# 17_PM8916_LDO.net
KiCad netlist of a schematic drawn in Altium Designer
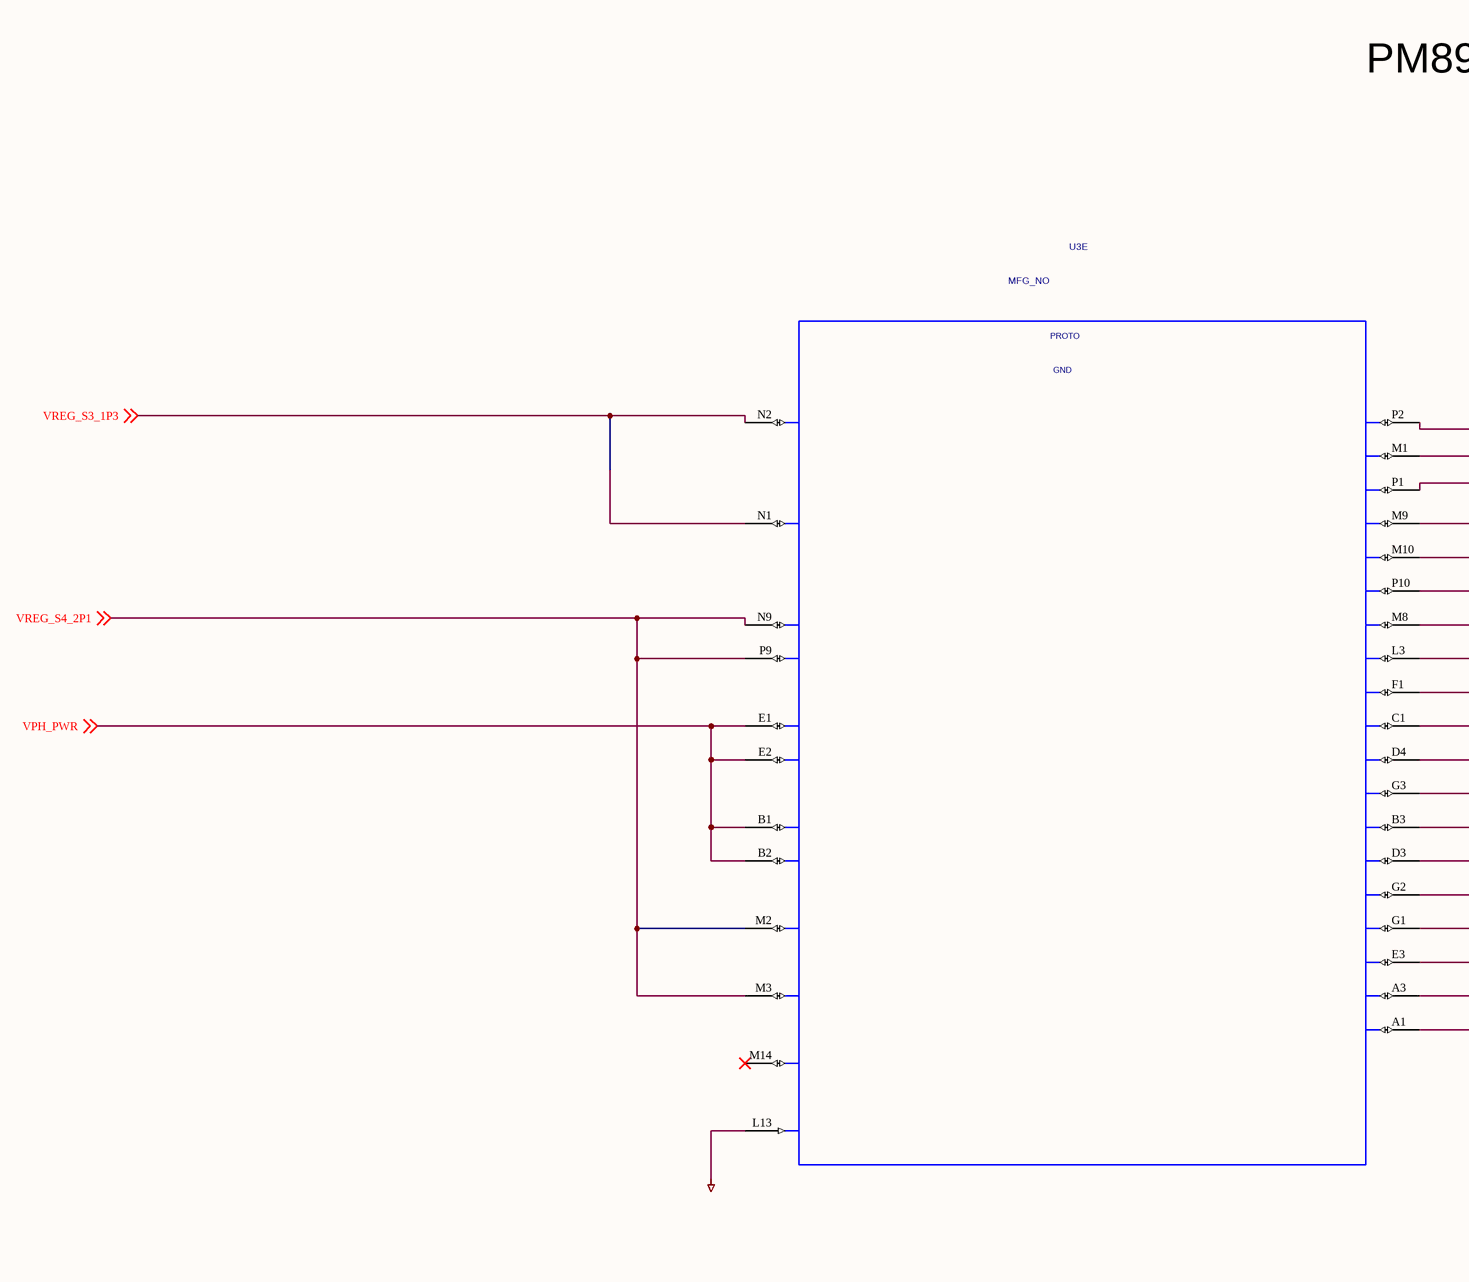
[diagram p0: 17 PM8916_LDO.SchDoc, top left]
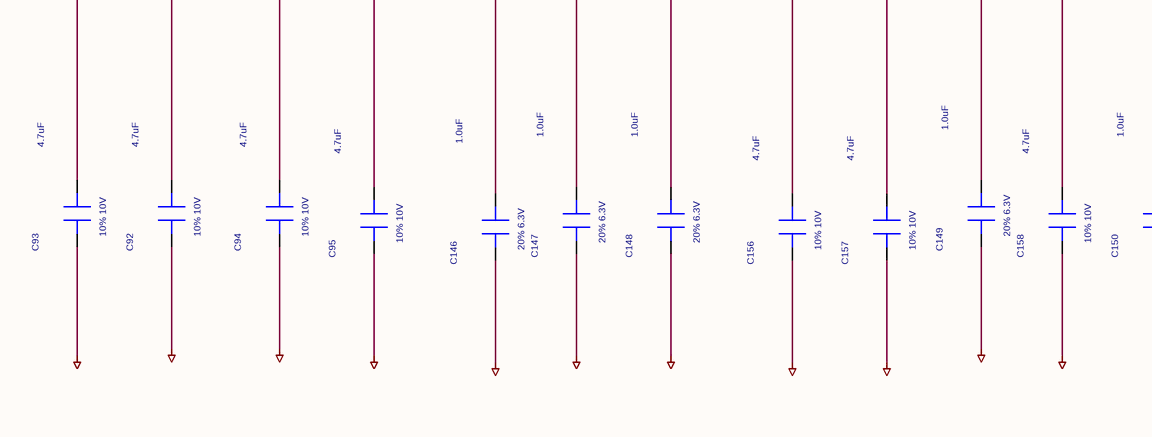
[diagram p1: 17 PM8916_LDO.SchDoc, top middle]
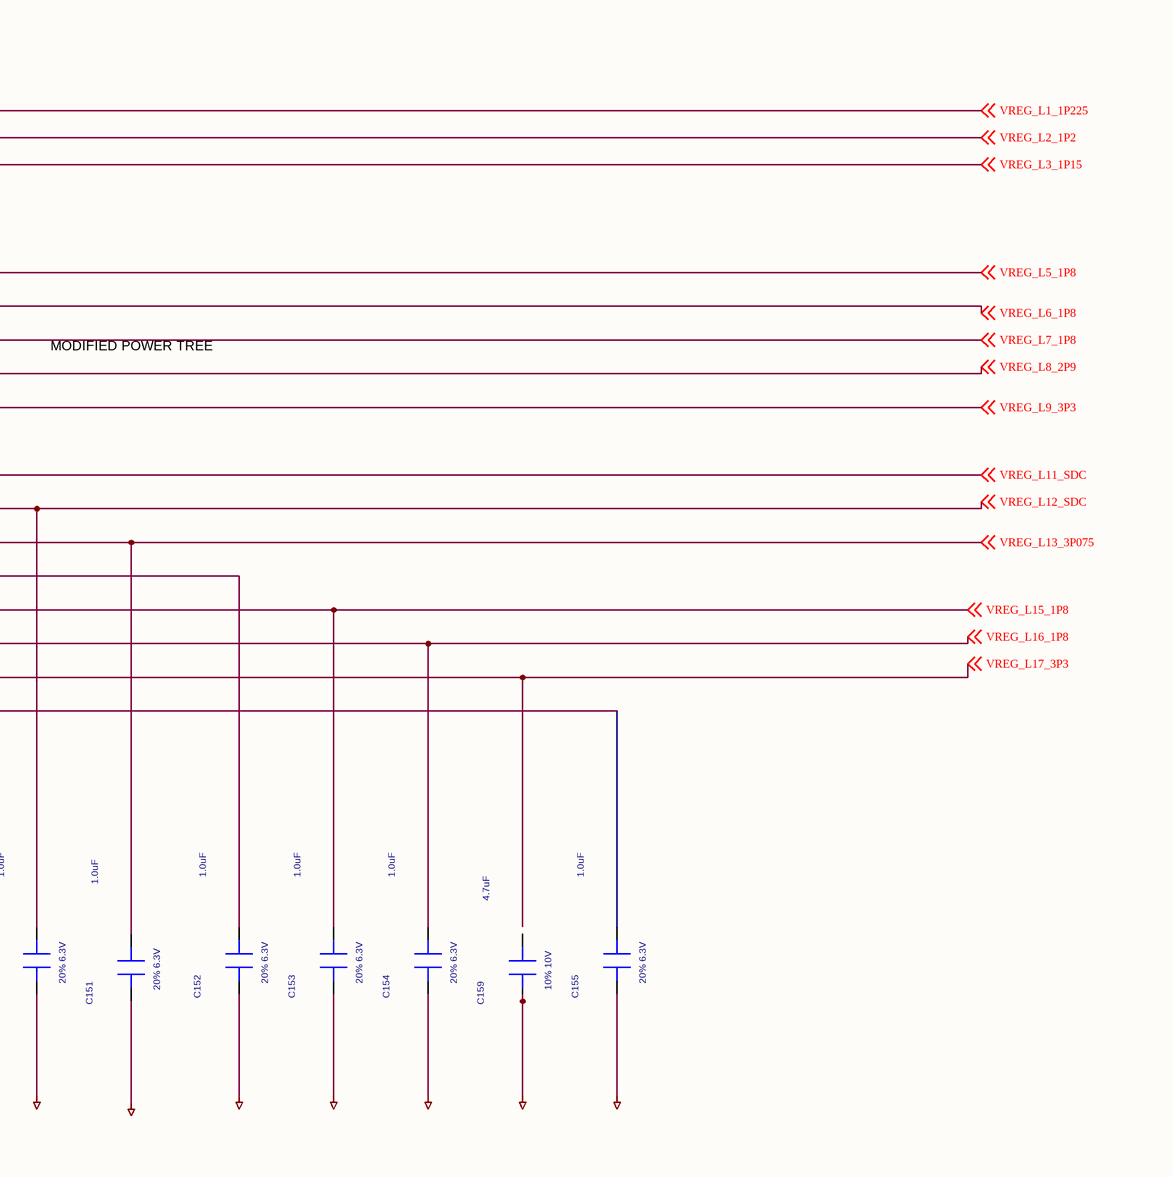
[diagram p2: 17 PM8916_LDO.SchDoc, top right]
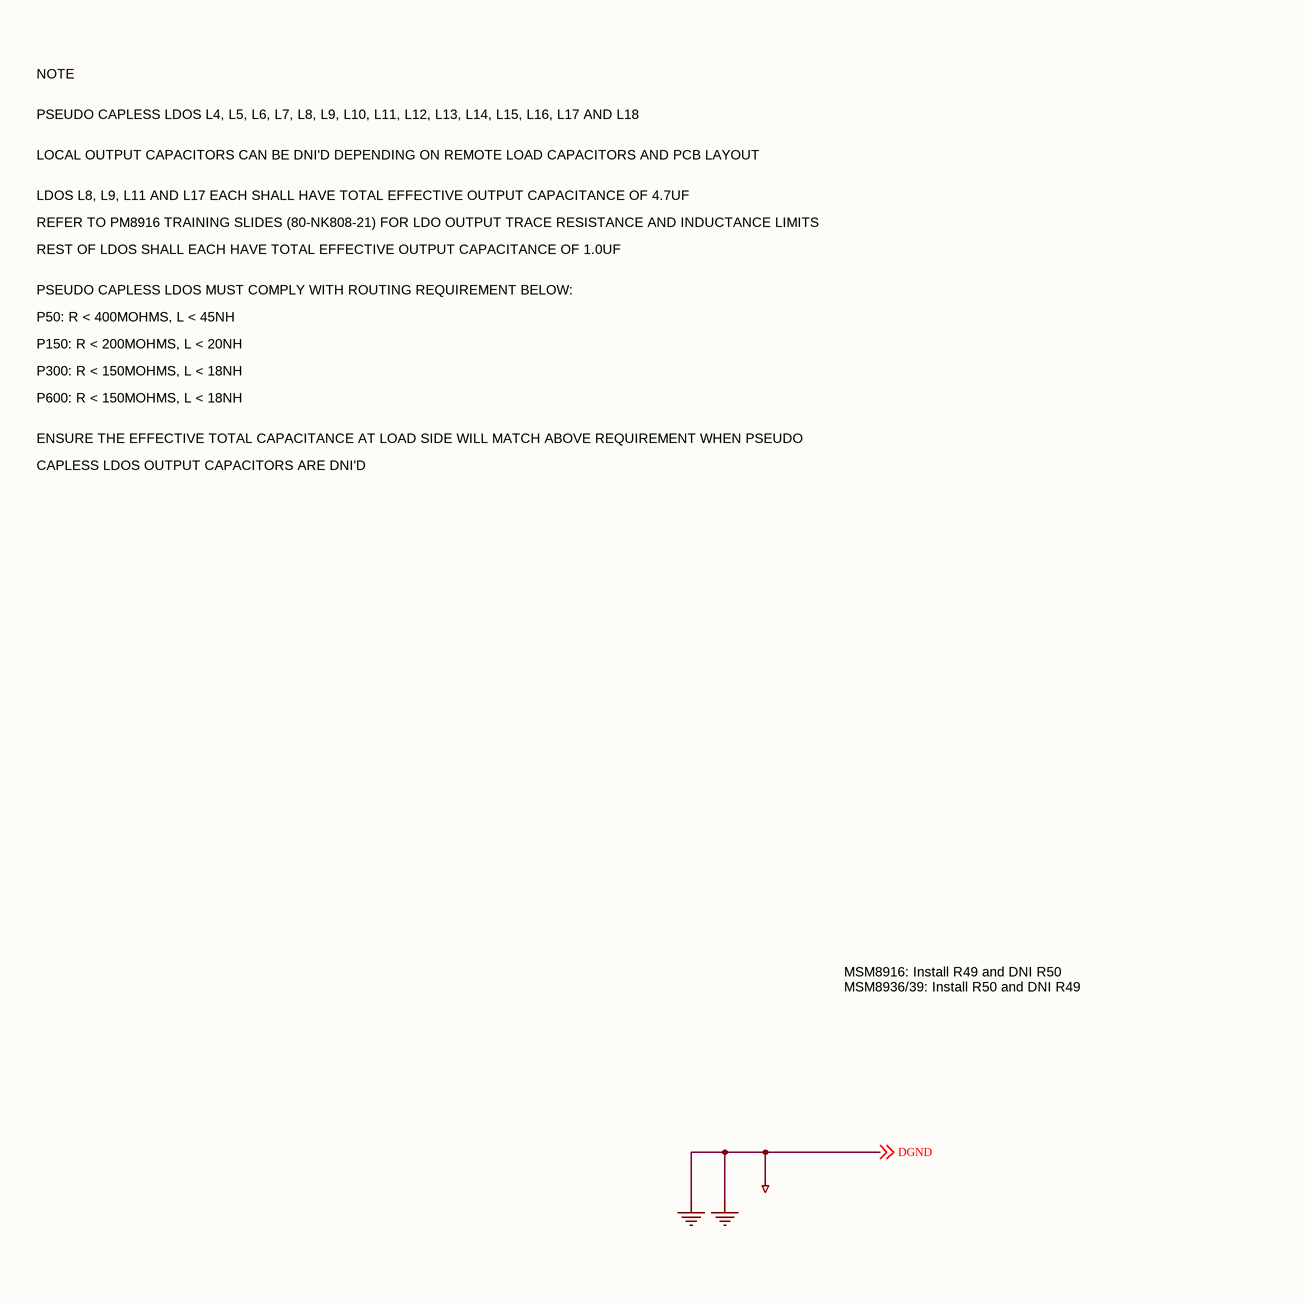
[diagram p3: 17 PM8916_LDO.SchDoc, bottom left]
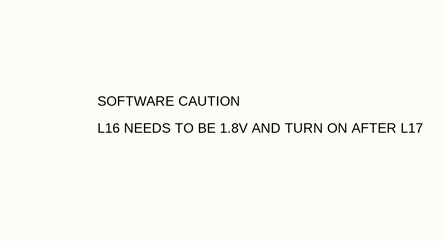
[diagram p4: 17 PM8916_LDO.SchDoc, bottom middle]
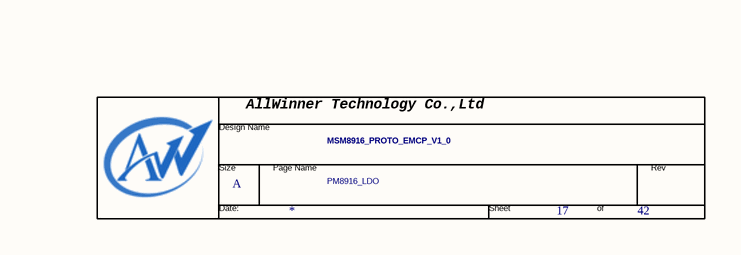
[diagram p5: 17 PM8916_LDO.SchDoc, bottom right]

(export (version "E")
  (design (tool "Eeschema 10.0.6"))
  (components
    (comp (ref "*")
      (value "TitleBlock0-AW")
      (fields
        (field (name "PAGE COUNT") "42")
        (field (name "PAGE NUMBER") "17")
        (field (name "PAGE SIZE") "A")
        (field (name "TITLE") "MSM8916_PROTO_EMCP_V1_0")
        (field (name "DOC") "PM8916_LDO")
      )
      (libsource (lib "*") (part "TitleBlock0-AW"))
    )
    (comp (ref "C92")
      (value "4.7uF")
      (fields (field (name "TOLERANCE") "10% 10V") (field (name "PART_NUMBER") "MCN_NO"))
      (libsource (lib "MSM8916_DRAM_PMIC_REF_Library") (part "CAP#1"))
    )
    (comp (ref "C93")
      (value "4.7uF")
      (fields (field (name "TOLERANCE") "10% 10V") (field (name "PART_NUMBER") "MCN_NO"))
      (libsource (lib "MSM8916_DRAM_PMIC_REF_Library") (part "CAP#1"))
    )
    (comp (ref "C94")
      (value "4.7uF")
      (fields (field (name "TOLERANCE") "10% 10V") (field (name "PART_NUMBER") "MCN_NO"))
      (libsource (lib "MSM8916_DRAM_PMIC_REF_Library") (part "CAP#1"))
    )
    (comp (ref "C95")
      (value "4.7uF")
      (fields (field (name "TOLERANCE") "10% 10V") (field (name "PART_NUMBER") "MCN_NO"))
      (libsource (lib "MSM8916_DRAM_PMIC_REF_Library") (part "CAP#1"))
    )
    (comp (ref "C146")
      (value "1.0uF")
      (fields (field (name "TOLERANCE") "20% 6.3V") (field (name "PART_NUMBER") "MCN_NO"))
      (libsource (lib "MSM8916_DRAM_PMIC_REF_Library") (part "CAP#1"))
    )
    (comp (ref "C147")
      (value "1.0uF")
      (fields (field (name "TOLERANCE") "20% 6.3V") (field (name "PART_NUMBER") "MCN_NO"))
      (libsource (lib "MSM8916_DRAM_PMIC_REF_Library") (part "CAP#1"))
    )
    (comp (ref "C148")
      (value "1.0uF")
      (fields (field (name "TOLERANCE") "20% 6.3V") (field (name "PART_NUMBER") "MCN_NO"))
      (libsource (lib "MSM8916_DRAM_PMIC_REF_Library") (part "CAP#1"))
    )
    (comp (ref "C149")
      (value "1.0uF")
      (fields (field (name "TOLERANCE") "20% 6.3V") (field (name "PART_NUMBER") "MCN_NO"))
      (libsource (lib "MSM8916_DRAM_PMIC_REF_Library") (part "CAP#1"))
    )
    (comp (ref "C150")
      (value "1.0uF")
      (fields (field (name "TOLERANCE") "20% 6.3V") (field (name "PART_NUMBER") "MCN_NO"))
      (libsource (lib "MSM8916_DRAM_PMIC_REF_Library") (part "CAP#1"))
    )
    (comp (ref "C151")
      (value "1.0uF")
      (fields (field (name "TOLERANCE") "20% 6.3V") (field (name "PART_NUMBER") "MCN_NO"))
      (libsource (lib "MSM8916_DRAM_PMIC_REF_Library") (part "CAP#1"))
    )
    (comp (ref "C152")
      (value "1.0uF")
      (fields (field (name "TOLERANCE") "20% 6.3V") (field (name "PART_NUMBER") "MCN_NO"))
      (libsource (lib "MSM8916_DRAM_PMIC_REF_Library") (part "CAP#1"))
    )
    (comp (ref "C153")
      (value "1.0uF")
      (fields (field (name "TOLERANCE") "20% 6.3V") (field (name "PART_NUMBER") "MCN_NO"))
      (libsource (lib "MSM8916_DRAM_PMIC_REF_Library") (part "CAP#1"))
    )
    (comp (ref "C154")
      (value "1.0uF")
      (fields (field (name "TOLERANCE") "20% 6.3V") (field (name "PART_NUMBER") "MCN_NO"))
      (libsource (lib "MSM8916_DRAM_PMIC_REF_Library") (part "CAP#1"))
    )
    (comp (ref "C155")
      (value "1.0uF")
      (fields (field (name "TOLERANCE") "20% 6.3V") (field (name "PART_NUMBER") "MCN_NO"))
      (libsource (lib "MSM8916_DRAM_PMIC_REF_Library") (part "CAP#1"))
    )
    (comp (ref "C156")
      (value "4.7uF")
      (fields (field (name "TOLERANCE") "10% 10V") (field (name "PART_NUMBER") "MCN_NO"))
      (libsource (lib "MSM8916_DRAM_PMIC_REF_Library") (part "CAP#1"))
    )
    (comp (ref "C157")
      (value "4.7uF")
      (fields (field (name "TOLERANCE") "10% 10V") (field (name "PART_NUMBER") "MCN_NO"))
      (libsource (lib "MSM8916_DRAM_PMIC_REF_Library") (part "CAP#1"))
    )
    (comp (ref "C158")
      (value "4.7uF")
      (fields (field (name "TOLERANCE") "10% 10V") (field (name "PART_NUMBER") "MCN_NO"))
      (libsource (lib "MSM8916_DRAM_PMIC_REF_Library") (part "CAP#1"))
    )
    (comp (ref "C159")
      (value "4.7uF")
      (fields (field (name "TOLERANCE") "10% 10V") (field (name "PART_NUMBER") "MCN_NO"))
      (libsource (lib "MSM8916_DRAM_PMIC_REF_Library") (part "CAP#1"))
    )
    (comp (ref "U3")
      (value "ASIC_PM8916")
      (footprint "PM-8916-0-176NSP-TR-00-0")
      (fields
        (field (name "SYMNAME") "GND")
        (field (name "PART_NUMBER") "MCN_NO")
        (field (name "PART_ID") "MFG_NO")
        (field (name "BLOCKID") "PROTO")
      )
      (libsource (lib "MSM8916_DRAM_PMIC_REF_Library") (part "ASIC_PM8916"))
    )
  )
  (nets
    (net (code "1") (name "DGND") (class "Default")
      (node (ref "C146") (pin "1") (pinfunction "POS_1") (pintype "bidirectional"))
      (node (ref "C147") (pin "1") (pinfunction "POS_1") (pintype "bidirectional"))
      (node (ref "C148") (pin "1") (pinfunction "POS_1") (pintype "bidirectional"))
      (node (ref "C149") (pin "1") (pinfunction "POS_1") (pintype "bidirectional"))
      (node (ref "C150") (pin "1") (pinfunction "POS_1") (pintype "bidirectional"))
      (node (ref "C151") (pin "1") (pinfunction "POS_1") (pintype "bidirectional"))
      (node (ref "C152") (pin "1") (pinfunction "POS_1") (pintype "bidirectional"))
      (node (ref "C153") (pin "1") (pinfunction "POS_1") (pintype "bidirectional"))
      (node (ref "C154") (pin "1") (pinfunction "POS_1") (pintype "bidirectional"))
      (node (ref "C155") (pin "1") (pinfunction "POS_1") (pintype "bidirectional"))
      (node (ref "C156") (pin "1") (pinfunction "POS_1") (pintype "bidirectional"))
      (node (ref "C157") (pin "1") (pinfunction "POS_1") (pintype "bidirectional"))
      (node (ref "C158") (pin "1") (pinfunction "POS_1") (pintype "bidirectional"))
      (node (ref "C159") (pin "1") (pinfunction "POS_1") (pintype "bidirectional"))
      (node (ref "C92") (pin "1") (pinfunction "POS_1") (pintype "bidirectional"))
      (node (ref "C93") (pin "1") (pinfunction "POS_1") (pintype "bidirectional"))
      (node (ref "C94") (pin "1") (pinfunction "POS_1") (pintype "bidirectional"))
      (node (ref "C95") (pin "1") (pinfunction "POS_1") (pintype "bidirectional"))
      (node (ref "U3") (pin "L13") (pinfunction "GND_DRV_L13") (pintype "input"))
    )
    (net (code "2") (name "Net-(C95-NEG)") (class "Default")
      (node (ref "C95") (pin "2") (pinfunction "NEG_2") (pintype "bidirectional"))
      (node (ref "U3") (pin "M10") (pinfunction "VREG_L4_2_M10") (pintype "bidirectional"))
      (node (ref "U3") (pin "M9") (pinfunction "VREG_L4_1_M9") (pintype "bidirectional"))
    )
    (net (code "3") (name "Net-(C149-NEG)") (class "Default")
      (node (ref "C149") (pin "2") (pinfunction "NEG_2") (pintype "bidirectional"))
      (node (ref "U3") (pin "D4") (pinfunction "VREG_L10_D4") (pintype "bidirectional"))
    )
    (net (code "4") (name "Net-(C152-NEG)") (class "Default")
      (node (ref "C152") (pin "2") (pinfunction "NEG_2") (pintype "bidirectional"))
      (node (ref "U3") (pin "G2") (pinfunction "VREG_L14_G2") (pintype "bidirectional"))
    )
    (net (code "5") (name "Net-(C155-NEG)") (class "Default")
      (node (ref "C155") (pin "2") (pinfunction "NEG_2") (pintype "bidirectional"))
      (node (ref "U3") (pin "A1") (pinfunction "VREG_L18_A1") (pintype "bidirectional"))
    )
    (net (code "6") (name "VPH_PWR") (class "Default")
      (node (ref "U3") (pin "B1") (pinfunction "VIN_GR5_A_B1") (pintype "bidirectional"))
      (node (ref "U3") (pin "B2") (pinfunction "VIN_GR5_B_B2") (pintype "bidirectional"))
      (node (ref "U3") (pin "E1") (pinfunction "VIN_GR4_A_E1") (pintype "bidirectional"))
      (node (ref "U3") (pin "E2") (pinfunction "VIN_GR4_B_E2") (pintype "bidirectional"))
    )
    (net (code "7") (name "VREG_L1_1P225") (class "Default")
      (node (ref "C93") (pin "2") (pinfunction "NEG_2") (pintype "bidirectional"))
      (node (ref "U3") (pin "P2") (pinfunction "VREG_L1_P2") (pintype "bidirectional"))
    )
    (net (code "8") (name "VREG_L2_1P2") (class "Default")
      (node (ref "C92") (pin "2") (pinfunction "NEG_2") (pintype "bidirectional"))
      (node (ref "U3") (pin "M1") (pinfunction "VREG_L2_M1") (pintype "bidirectional"))
    )
    (net (code "9") (name "VREG_L3_1P15") (class "Default")
      (node (ref "C94") (pin "2") (pinfunction "NEG_2") (pintype "bidirectional"))
      (node (ref "U3") (pin "P1") (pinfunction "VREG_L3_P1") (pintype "bidirectional"))
    )
    (net (code "10") (name "VREG_L5_1P8") (class "Default")
      (node (ref "C146") (pin "2") (pinfunction "NEG_2") (pintype "bidirectional"))
      (node (ref "U3") (pin "P10") (pinfunction "VREG_L5_P10") (pintype "bidirectional"))
    )
    (net (code "11") (name "VREG_L6_1P8") (class "Default")
      (node (ref "C147") (pin "2") (pinfunction "NEG_2") (pintype "bidirectional"))
      (node (ref "U3") (pin "M8") (pinfunction "VREG_L6_M8") (pintype "bidirectional"))
    )
    (net (code "12") (name "VREG_L7_1P8") (class "Default")
      (node (ref "C148") (pin "2") (pinfunction "NEG_2") (pintype "bidirectional"))
      (node (ref "U3") (pin "L3") (pinfunction "VREG_L7_L3") (pintype "bidirectional"))
    )
    (net (code "13") (name "VREG_L8_2P9") (class "Default")
      (node (ref "C156") (pin "2") (pinfunction "NEG_2") (pintype "bidirectional"))
      (node (ref "U3") (pin "F1") (pinfunction "VREG_L8_F1") (pintype "bidirectional"))
    )
    (net (code "14") (name "VREG_L9_3P3") (class "Default")
      (node (ref "C157") (pin "2") (pinfunction "NEG_2") (pintype "bidirectional"))
      (node (ref "U3") (pin "C1") (pinfunction "VREG_L9_C1") (pintype "bidirectional"))
    )
    (net (code "15") (name "VREG_L11_SDC") (class "Default")
      (node (ref "C158") (pin "2") (pinfunction "NEG_2") (pintype "bidirectional"))
      (node (ref "U3") (pin "G3") (pinfunction "VREG_L11_G3") (pintype "bidirectional"))
    )
    (net (code "16") (name "VREG_L12_SDC") (class "Default")
      (node (ref "C150") (pin "2") (pinfunction "NEG_2") (pintype "bidirectional"))
      (node (ref "U3") (pin "B3") (pinfunction "VREG_L12_B3") (pintype "bidirectional"))
    )
    (net (code "17") (name "VREG_L13_3P075") (class "Default")
      (node (ref "C151") (pin "2") (pinfunction "NEG_2") (pintype "bidirectional"))
      (node (ref "U3") (pin "D3") (pinfunction "VREG_L13_D3") (pintype "bidirectional"))
    )
    (net (code "18") (name "VREG_L15_1P8") (class "Default")
      (node (ref "C153") (pin "2") (pinfunction "NEG_2") (pintype "bidirectional"))
      (node (ref "U3") (pin "G1") (pinfunction "VREG_L15_G1") (pintype "bidirectional"))
    )
    (net (code "19") (name "VREG_L16_1P8") (class "Default")
      (node (ref "C154") (pin "2") (pinfunction "NEG_2") (pintype "bidirectional"))
      (node (ref "U3") (pin "E3") (pinfunction "VREG_L16_E3") (pintype "bidirectional"))
    )
    (net (code "20") (name "VREG_L17_3P3") (class "Default")
      (node (ref "U3") (pin "A3") (pinfunction "VREG_L17_A3") (pintype "bidirectional"))
    )
    (net (code "21") (name "VREG_S3_1P3") (class "Default")
      (node (ref "U3") (pin "N1") (pinfunction "VIN_GR2_N1") (pintype "bidirectional"))
      (node (ref "U3") (pin "N2") (pinfunction "VIN_GR1_N2") (pintype "bidirectional"))
    )
    (net (code "22") (name "VREG_S4_2P1") (class "Default")
      (node (ref "U3") (pin "M2") (pinfunction "VIN_GR6_M2") (pintype "bidirectional"))
      (node (ref "U3") (pin "M3") (pinfunction "VIN_GR7_M3") (pintype "bidirectional"))
      (node (ref "U3") (pin "N9") (pinfunction "VIN_GR3_A_N9") (pintype "bidirectional"))
      (node (ref "U3") (pin "P9") (pinfunction "VIN_GR3_B_P9") (pintype "bidirectional"))
    )
    (net (code "23") (name "unconnected-(C159-NEG-Pad2)") (class "Default")
      (node (ref "C159") (pin "2") (pinfunction "NEG_2") (pintype "bidirectional"))
    )
    (net (code "24") (name "unconnected-(U3E-VIB_DRV*-PadM14)") (class "Default")
      (node (ref "U3") (pin "M14") (pinfunction "VIB_DRV*_M14") (pintype "bidirectional+no_connect"))
    )
  )
)
